# date-led-r1.net
KiCad netlist of a schematic drawn in EAGLE
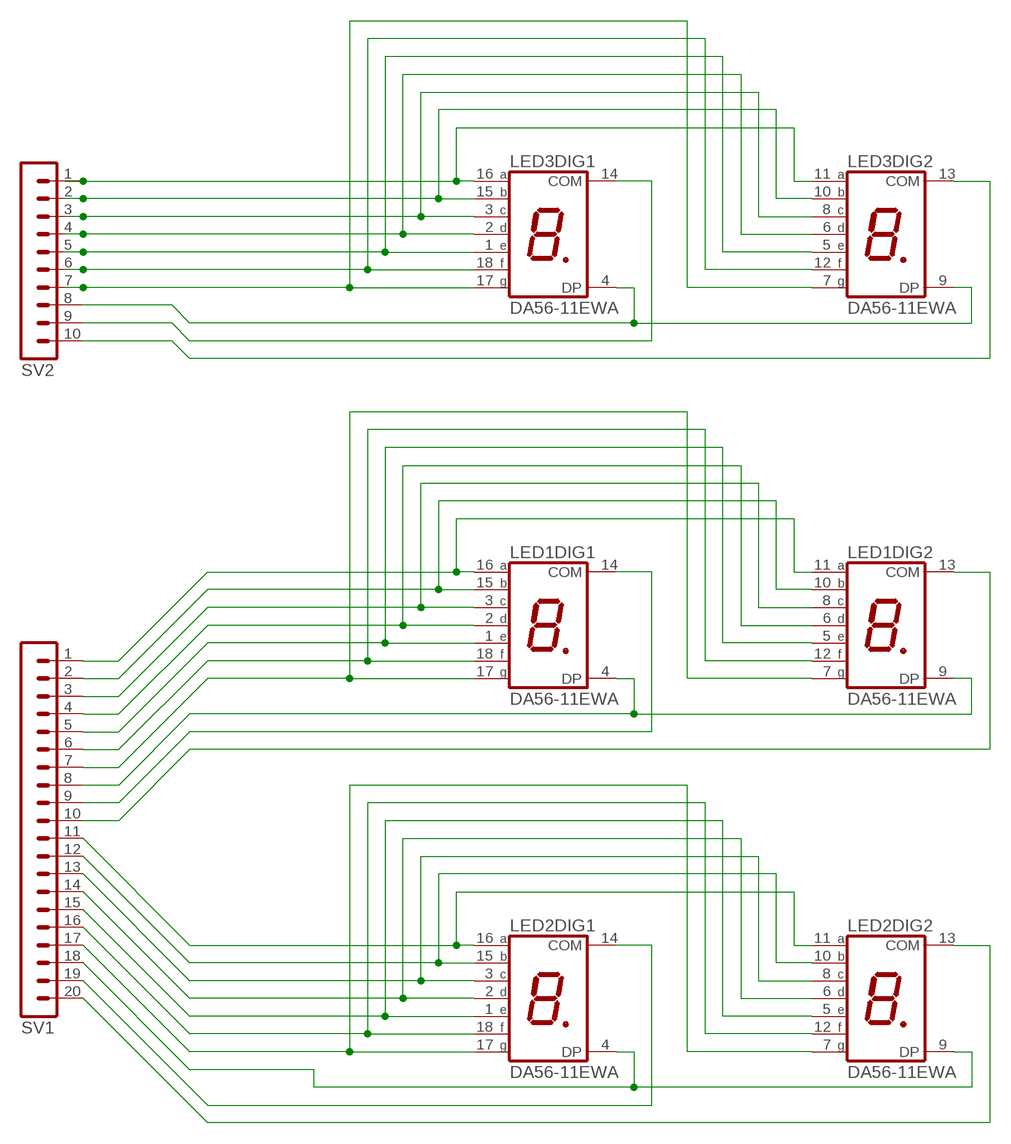
[diagram p0: schematic, sheet 1]

(export (version "E")
  (design (tool "Eeschema 10.0.6"))
  (components
    (comp (ref "LED1")
      (value "DA56-11EWA")
      (footprint "eagle-import:DA56")
      (libsource (lib "eagle-import") (part "DA56-11EWA"))
    )
    (comp (ref "LED2")
      (value "DA56-11EWA")
      (footprint "eagle-import:DA56")
      (libsource (lib "eagle-import") (part "DA56-11EWA"))
    )
    (comp (ref "LED3")
      (value "DA56-11EWA")
      (footprint "eagle-import:DA56")
      (libsource (lib "eagle-import") (part "DA56-11EWA"))
    )
    (comp (ref "SV1")
      (value "MA20-1W")
      (footprint "eagle-import:MA20-1W")
      (libsource (lib "eagle-import") (part "MA20-1W"))
    )
    (comp (ref "SV2")
      (value "MA10-1W")
      (footprint "eagle-import:MA10-1W")
      (libsource (lib "eagle-import") (part "MA10-1W"))
    )
  )
  (nets
    (net (code "1") (name "Net-(LED1A-A)") (class "Default")
      (node (ref "LED1") (pin "11") (pinfunction "A_11") (pintype "passive"))
      (node (ref "LED1") (pin "16") (pinfunction "A_16") (pintype "passive"))
      (node (ref "SV1") (pin "1") (pinfunction "1_1") (pintype "passive"))
    )
    (net (code "2") (name "Net-(LED1A-B)") (class "Default")
      (node (ref "LED1") (pin "10") (pinfunction "B_10") (pintype "passive"))
      (node (ref "LED1") (pin "15") (pinfunction "B_15") (pintype "passive"))
      (node (ref "SV1") (pin "2") (pinfunction "2_2") (pintype "passive"))
    )
    (net (code "3") (name "Net-(LED1A-C)") (class "Default")
      (node (ref "LED1") (pin "3") (pinfunction "C_3") (pintype "passive"))
      (node (ref "LED1") (pin "8") (pinfunction "C_8") (pintype "passive"))
      (node (ref "SV1") (pin "3") (pinfunction "3_3") (pintype "passive"))
    )
    (net (code "4") (name "Net-(LED1A-COM)") (class "Default")
      (node (ref "LED1") (pin "14") (pinfunction "COM_14") (pintype "passive"))
      (node (ref "SV1") (pin "9") (pinfunction "9_9") (pintype "passive"))
    )
    (net (code "5") (name "Net-(LED1A-D)") (class "Default")
      (node (ref "LED1") (pin "2") (pinfunction "D_2") (pintype "passive"))
      (node (ref "LED1") (pin "6") (pinfunction "D_6") (pintype "passive"))
      (node (ref "SV1") (pin "4") (pinfunction "4_4") (pintype "passive"))
    )
    (net (code "6") (name "Net-(LED1A-DP)") (class "Default")
      (node (ref "LED1") (pin "4") (pinfunction "DP_4") (pintype "passive"))
      (node (ref "LED1") (pin "9") (pinfunction "DP_9") (pintype "passive"))
      (node (ref "SV1") (pin "8") (pinfunction "8_8") (pintype "passive"))
    )
    (net (code "7") (name "Net-(LED1A-E)") (class "Default")
      (node (ref "LED1") (pin "1") (pinfunction "E_1") (pintype "passive"))
      (node (ref "LED1") (pin "5") (pinfunction "E_5") (pintype "passive"))
      (node (ref "SV1") (pin "5") (pinfunction "5_5") (pintype "passive"))
    )
    (net (code "8") (name "Net-(LED1A-F)") (class "Default")
      (node (ref "LED1") (pin "12") (pinfunction "F_12") (pintype "passive"))
      (node (ref "LED1") (pin "18") (pinfunction "F_18") (pintype "passive"))
      (node (ref "SV1") (pin "6") (pinfunction "6_6") (pintype "passive"))
    )
    (net (code "9") (name "Net-(LED1A-G)") (class "Default")
      (node (ref "LED1") (pin "17") (pinfunction "G_17") (pintype "passive"))
      (node (ref "LED1") (pin "7") (pinfunction "G_7") (pintype "passive"))
      (node (ref "SV1") (pin "7") (pinfunction "7_7") (pintype "passive"))
    )
    (net (code "10") (name "Net-(LED1B-COM)") (class "Default")
      (node (ref "LED1") (pin "13") (pinfunction "COM_13") (pintype "passive"))
      (node (ref "SV1") (pin "10") (pinfunction "10_10") (pintype "passive"))
    )
    (net (code "11") (name "Net-(LED2A-A)") (class "Default")
      (node (ref "LED2") (pin "11") (pinfunction "A_11") (pintype "passive"))
      (node (ref "LED2") (pin "16") (pinfunction "A_16") (pintype "passive"))
      (node (ref "SV1") (pin "11") (pinfunction "11_11") (pintype "passive"))
    )
    (net (code "12") (name "Net-(LED2A-B)") (class "Default")
      (node (ref "LED2") (pin "10") (pinfunction "B_10") (pintype "passive"))
      (node (ref "LED2") (pin "15") (pinfunction "B_15") (pintype "passive"))
      (node (ref "SV1") (pin "12") (pinfunction "12_12") (pintype "passive"))
    )
    (net (code "13") (name "Net-(LED2A-C)") (class "Default")
      (node (ref "LED2") (pin "3") (pinfunction "C_3") (pintype "passive"))
      (node (ref "LED2") (pin "8") (pinfunction "C_8") (pintype "passive"))
      (node (ref "SV1") (pin "13") (pinfunction "13_13") (pintype "passive"))
    )
    (net (code "14") (name "Net-(LED2A-COM)") (class "Default")
      (node (ref "LED2") (pin "14") (pinfunction "COM_14") (pintype "passive"))
      (node (ref "SV1") (pin "19") (pinfunction "19_19") (pintype "passive"))
    )
    (net (code "15") (name "Net-(LED2A-D)") (class "Default")
      (node (ref "LED2") (pin "2") (pinfunction "D_2") (pintype "passive"))
      (node (ref "LED2") (pin "6") (pinfunction "D_6") (pintype "passive"))
      (node (ref "SV1") (pin "14") (pinfunction "14_14") (pintype "passive"))
    )
    (net (code "16") (name "Net-(LED2A-DP)") (class "Default")
      (node (ref "LED2") (pin "4") (pinfunction "DP_4") (pintype "passive"))
      (node (ref "LED2") (pin "9") (pinfunction "DP_9") (pintype "passive"))
      (node (ref "SV1") (pin "18") (pinfunction "18_18") (pintype "passive"))
    )
    (net (code "17") (name "Net-(LED2A-E)") (class "Default")
      (node (ref "LED2") (pin "1") (pinfunction "E_1") (pintype "passive"))
      (node (ref "LED2") (pin "5") (pinfunction "E_5") (pintype "passive"))
      (node (ref "SV1") (pin "15") (pinfunction "15_15") (pintype "passive"))
    )
    (net (code "18") (name "Net-(LED2A-F)") (class "Default")
      (node (ref "LED2") (pin "12") (pinfunction "F_12") (pintype "passive"))
      (node (ref "LED2") (pin "18") (pinfunction "F_18") (pintype "passive"))
      (node (ref "SV1") (pin "16") (pinfunction "16_16") (pintype "passive"))
    )
    (net (code "19") (name "Net-(LED2A-G)") (class "Default")
      (node (ref "LED2") (pin "17") (pinfunction "G_17") (pintype "passive"))
      (node (ref "LED2") (pin "7") (pinfunction "G_7") (pintype "passive"))
      (node (ref "SV1") (pin "17") (pinfunction "17_17") (pintype "passive"))
    )
    (net (code "20") (name "Net-(LED2B-COM)") (class "Default")
      (node (ref "LED2") (pin "13") (pinfunction "COM_13") (pintype "passive"))
      (node (ref "SV1") (pin "20") (pinfunction "20_20") (pintype "passive"))
    )
    (net (code "21") (name "Net-(LED3A-A)") (class "Default")
      (node (ref "LED3") (pin "11") (pinfunction "A_11") (pintype "passive"))
      (node (ref "LED3") (pin "16") (pinfunction "A_16") (pintype "passive"))
      (node (ref "SV2") (pin "1") (pinfunction "1_1") (pintype "passive"))
    )
    (net (code "22") (name "Net-(LED3A-B)") (class "Default")
      (node (ref "LED3") (pin "10") (pinfunction "B_10") (pintype "passive"))
      (node (ref "LED3") (pin "15") (pinfunction "B_15") (pintype "passive"))
      (node (ref "SV2") (pin "2") (pinfunction "2_2") (pintype "passive"))
    )
    (net (code "23") (name "Net-(LED3A-C)") (class "Default")
      (node (ref "LED3") (pin "3") (pinfunction "C_3") (pintype "passive"))
      (node (ref "LED3") (pin "8") (pinfunction "C_8") (pintype "passive"))
      (node (ref "SV2") (pin "3") (pinfunction "3_3") (pintype "passive"))
    )
    (net (code "24") (name "Net-(LED3A-COM)") (class "Default")
      (node (ref "LED3") (pin "14") (pinfunction "COM_14") (pintype "passive"))
      (node (ref "SV2") (pin "9") (pinfunction "9_9") (pintype "passive"))
    )
    (net (code "25") (name "Net-(LED3A-D)") (class "Default")
      (node (ref "LED3") (pin "2") (pinfunction "D_2") (pintype "passive"))
      (node (ref "LED3") (pin "6") (pinfunction "D_6") (pintype "passive"))
      (node (ref "SV2") (pin "4") (pinfunction "4_4") (pintype "passive"))
    )
    (net (code "26") (name "Net-(LED3A-DP)") (class "Default")
      (node (ref "LED3") (pin "4") (pinfunction "DP_4") (pintype "passive"))
      (node (ref "LED3") (pin "9") (pinfunction "DP_9") (pintype "passive"))
      (node (ref "SV2") (pin "8") (pinfunction "8_8") (pintype "passive"))
    )
    (net (code "27") (name "Net-(LED3A-E)") (class "Default")
      (node (ref "LED3") (pin "1") (pinfunction "E_1") (pintype "passive"))
      (node (ref "LED3") (pin "5") (pinfunction "E_5") (pintype "passive"))
      (node (ref "SV2") (pin "5") (pinfunction "5_5") (pintype "passive"))
    )
    (net (code "28") (name "Net-(LED3A-F)") (class "Default")
      (node (ref "LED3") (pin "12") (pinfunction "F_12") (pintype "passive"))
      (node (ref "LED3") (pin "18") (pinfunction "F_18") (pintype "passive"))
      (node (ref "SV2") (pin "6") (pinfunction "6_6") (pintype "passive"))
    )
    (net (code "29") (name "Net-(LED3A-G)") (class "Default")
      (node (ref "LED3") (pin "17") (pinfunction "G_17") (pintype "passive"))
      (node (ref "LED3") (pin "7") (pinfunction "G_7") (pintype "passive"))
      (node (ref "SV2") (pin "7") (pinfunction "7_7") (pintype "passive"))
    )
    (net (code "30") (name "Net-(LED3B-COM)") (class "Default")
      (node (ref "LED3") (pin "13") (pinfunction "COM_13") (pintype "passive"))
      (node (ref "SV2") (pin "10") (pinfunction "10_10") (pintype "passive"))
    )
  )
)
